# BRAIN2_Breakout_SW.net
KiCad netlist of a schematic drawn in EAGLE
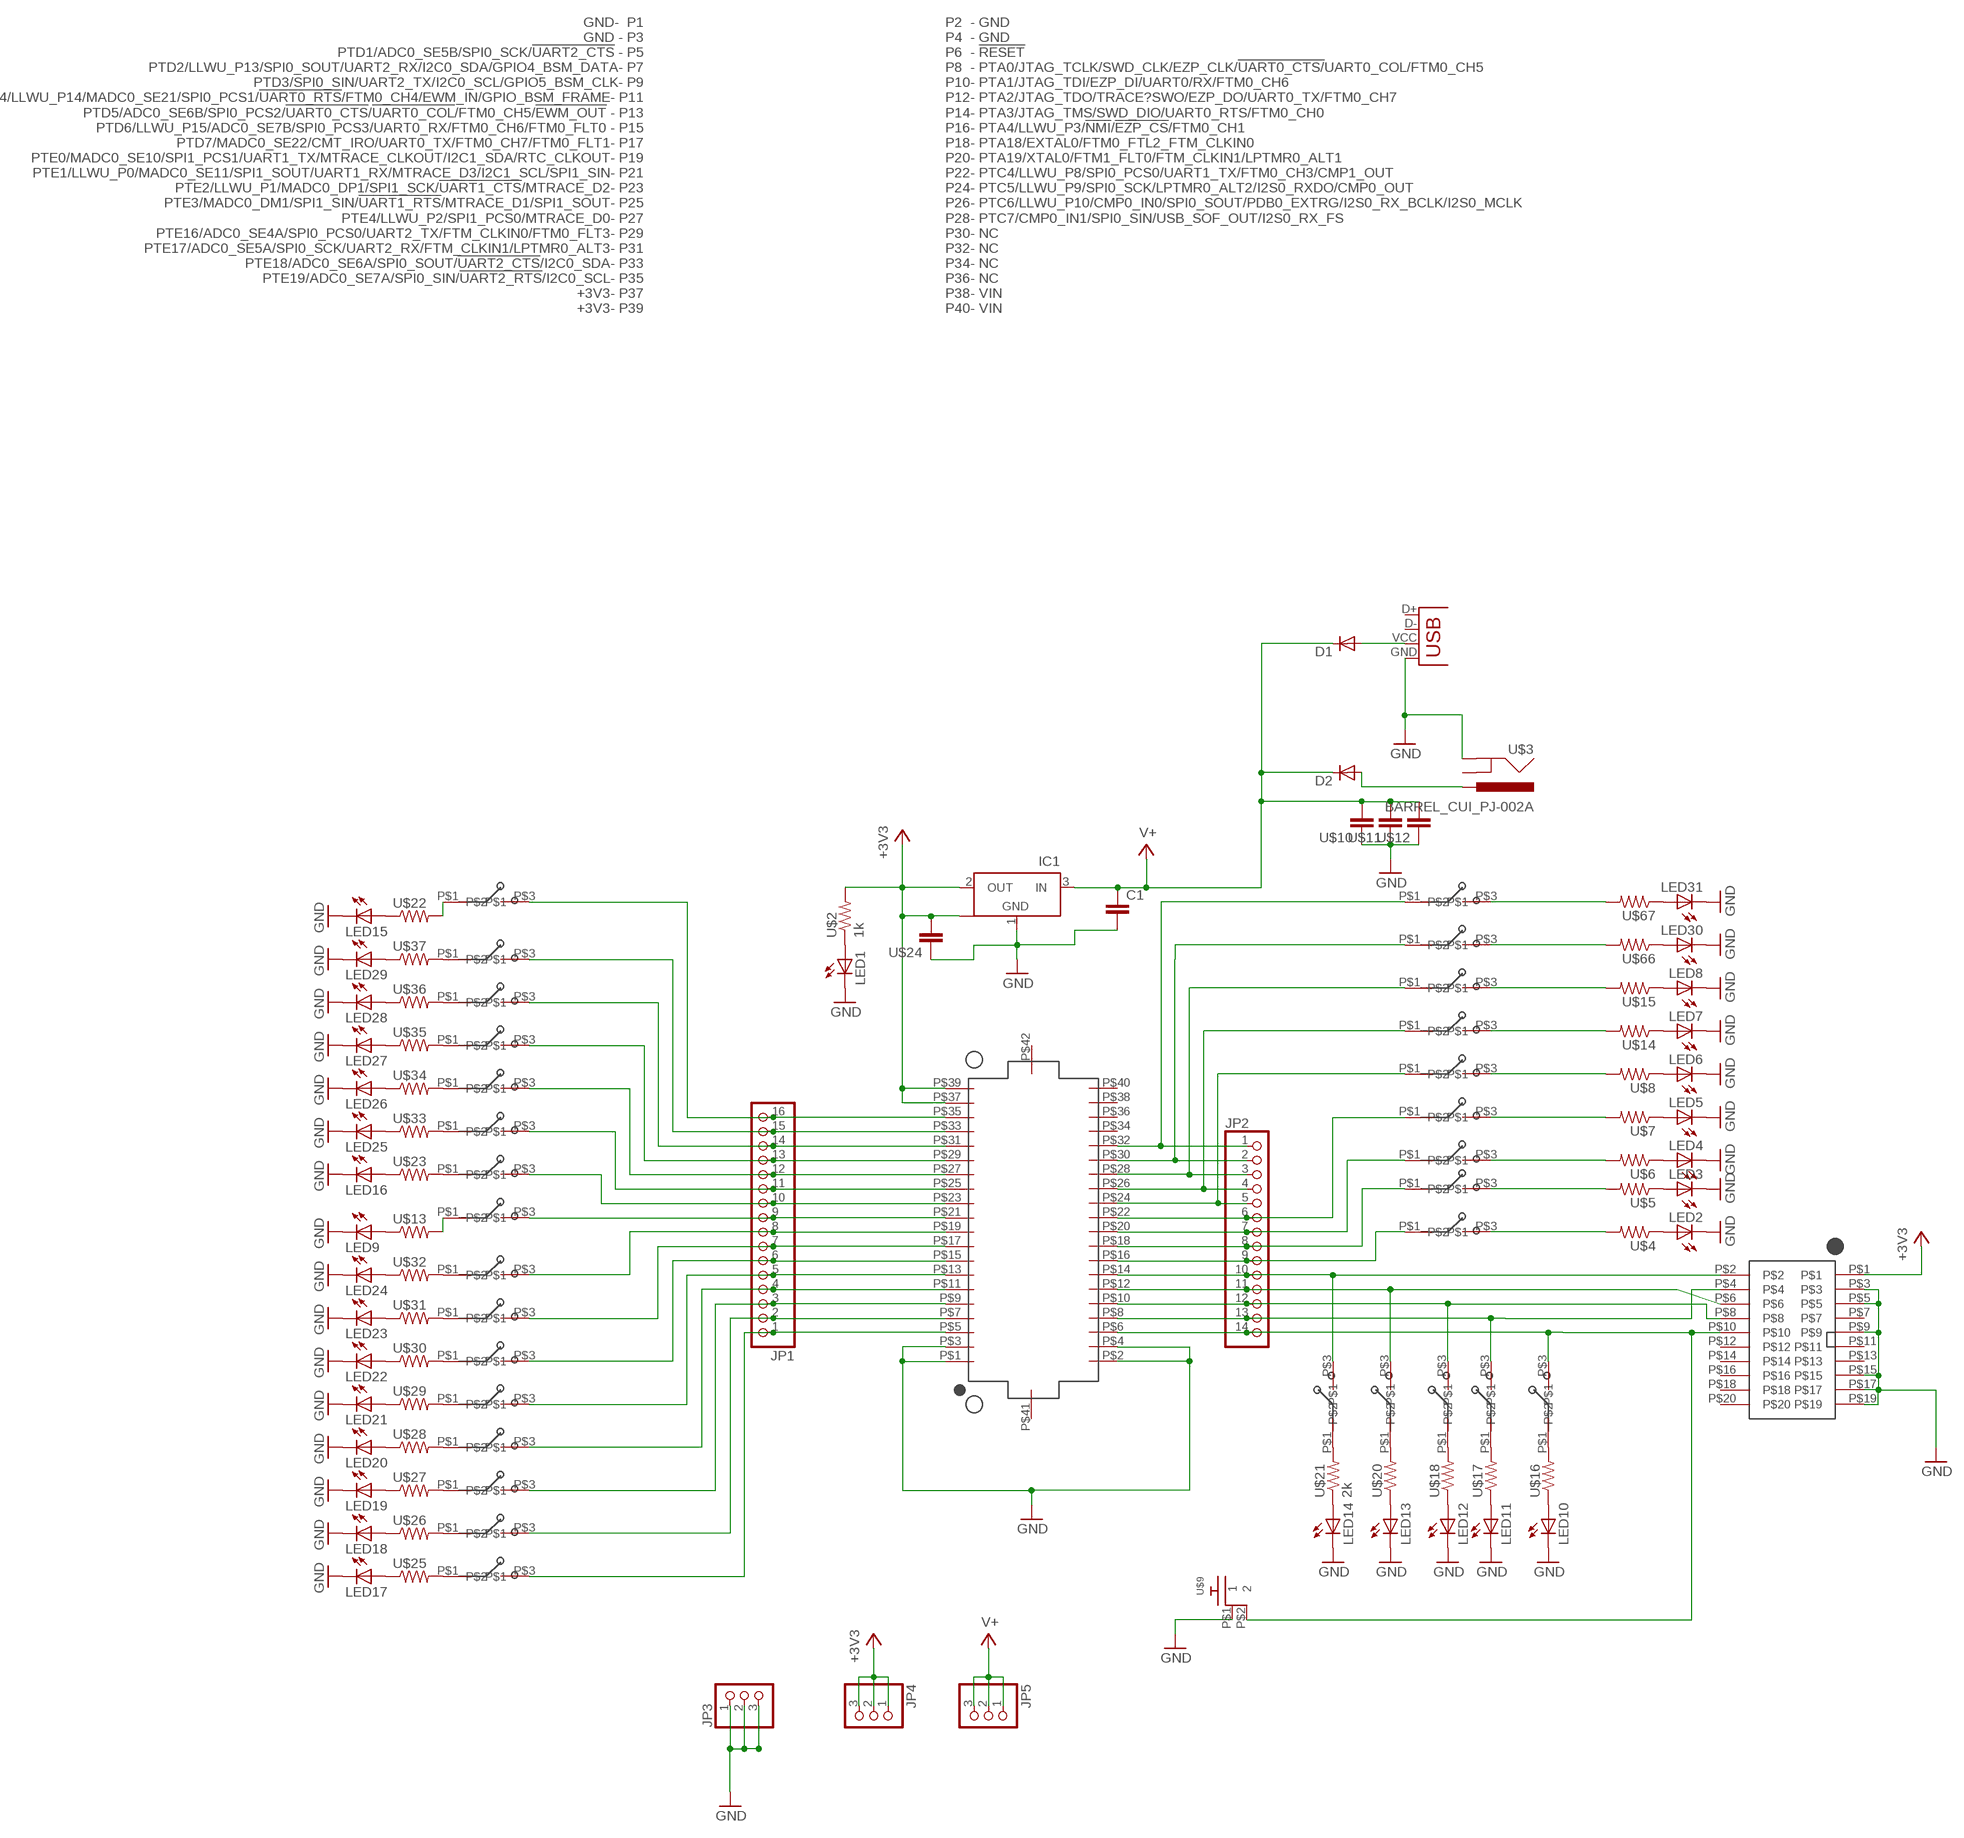
[diagram p0: schematic, sheet 1]

(export (version "E")
  (design (tool "Eeschema 10.0.6"))
  (components
    (comp (ref "C1")
      (value "RF-C0805")
      (footprint "eagle-import:C0805")
      (libsource (lib "eagle-import") (part "RF-C0805"))
    )
    (comp (ref "D1")
      (value "DIODESMA")
      (footprint "eagle-import:SMA-DIODE")
      (libsource (lib "eagle-import") (part "DIODESMA"))
    )
    (comp (ref "D2")
      (value "DIODESMA")
      (footprint "eagle-import:SMA-DIODE")
      (libsource (lib "eagle-import") (part "DIODESMA"))
    )
    (comp (ref "IC1")
      (value "NCP1117ST33T3G_1")
      (footprint "eagle-import:SOT223")
      (fields (field (name "MFGN") "OnSemi") (field (name "MFGP") "NCP1117ST33T3G"))
      (libsource (lib "eagle-import") (part "NCP1117ST33T3G_1"))
    )
    (comp (ref "JP1")
      (value "PINHD-1X16")
      (footprint "eagle-import:1X16")
      (libsource (lib "eagle-import") (part "PINHD-1X16"))
    )
    (comp (ref "JP2")
      (value "PINHD-1X14")
      (footprint "eagle-import:1X14")
      (libsource (lib "eagle-import") (part "PINHD-1X14"))
    )
    (comp (ref "JP3")
      (value "PINHD-1X3")
      (footprint "eagle-import:1X03")
      (libsource (lib "eagle-import") (part "PINHD-1X3"))
    )
    (comp (ref "JP4")
      (value "PINHD-1X3")
      (footprint "eagle-import:1X03")
      (libsource (lib "eagle-import") (part "PINHD-1X3"))
    )
    (comp (ref "JP5")
      (value "PINHD-1X3")
      (footprint "eagle-import:1X03")
      (libsource (lib "eagle-import") (part "PINHD-1X3"))
    )
    (comp (ref "LED1")
      (value "LEDCHIP-LED0805")
      (footprint "eagle-import:CHIP-LED0805")
      (fields (field (name "MFGN") "Wurth Electronics Inc") (field (name "MFGP") "150080BS75000"))
      (libsource (lib "eagle-import") (part "LEDCHIP-LED0805"))
    )
    (comp (ref "LED2")
      (value "LEDCHIP-LED0805")
      (footprint "eagle-import:CHIP-LED0805")
      (libsource (lib "eagle-import") (part "LEDCHIP-LED0805"))
    )
    (comp (ref "LED3")
      (value "LEDCHIP-LED0805")
      (footprint "eagle-import:CHIP-LED0805")
      (libsource (lib "eagle-import") (part "LEDCHIP-LED0805"))
    )
    (comp (ref "LED4")
      (value "LEDCHIP-LED0805")
      (footprint "eagle-import:CHIP-LED0805")
      (libsource (lib "eagle-import") (part "LEDCHIP-LED0805"))
    )
    (comp (ref "LED5")
      (value "LEDCHIP-LED0805")
      (footprint "eagle-import:CHIP-LED0805")
      (libsource (lib "eagle-import") (part "LEDCHIP-LED0805"))
    )
    (comp (ref "LED6")
      (value "LEDCHIP-LED0805")
      (footprint "eagle-import:CHIP-LED0805")
      (libsource (lib "eagle-import") (part "LEDCHIP-LED0805"))
    )
    (comp (ref "LED7")
      (value "LEDCHIP-LED0805")
      (footprint "eagle-import:CHIP-LED0805")
      (libsource (lib "eagle-import") (part "LEDCHIP-LED0805"))
    )
    (comp (ref "LED8")
      (value "LEDCHIP-LED0805")
      (footprint "eagle-import:CHIP-LED0805")
      (libsource (lib "eagle-import") (part "LEDCHIP-LED0805"))
    )
    (comp (ref "LED9")
      (value "LEDCHIP-LED0805")
      (footprint "eagle-import:CHIP-LED0805")
      (libsource (lib "eagle-import") (part "LEDCHIP-LED0805"))
    )
    (comp (ref "LED10")
      (value "LEDCHIP-LED0805")
      (footprint "eagle-import:CHIP-LED0805")
      (libsource (lib "eagle-import") (part "LEDCHIP-LED0805"))
    )
    (comp (ref "LED11")
      (value "LEDCHIP-LED0805")
      (footprint "eagle-import:CHIP-LED0805")
      (libsource (lib "eagle-import") (part "LEDCHIP-LED0805"))
    )
    (comp (ref "LED12")
      (value "LEDCHIP-LED0805")
      (footprint "eagle-import:CHIP-LED0805")
      (libsource (lib "eagle-import") (part "LEDCHIP-LED0805"))
    )
    (comp (ref "LED13")
      (value "LEDCHIP-LED0805")
      (footprint "eagle-import:CHIP-LED0805")
      (libsource (lib "eagle-import") (part "LEDCHIP-LED0805"))
    )
    (comp (ref "LED14")
      (value "LEDCHIP-LED0805")
      (footprint "eagle-import:CHIP-LED0805")
      (libsource (lib "eagle-import") (part "LEDCHIP-LED0805"))
    )
    (comp (ref "LED15")
      (value "LEDCHIP-LED0805")
      (footprint "eagle-import:CHIP-LED0805")
      (fields (field (name "MFGN") "Kingbright") (field (name "MFGP") "APT2012SECK"))
      (libsource (lib "eagle-import") (part "LEDCHIP-LED0805"))
    )
    (comp (ref "LED16")
      (value "LEDCHIP-LED0805")
      (footprint "eagle-import:CHIP-LED0805")
      (libsource (lib "eagle-import") (part "LEDCHIP-LED0805"))
    )
    (comp (ref "LED17")
      (value "LEDCHIP-LED0805")
      (footprint "eagle-import:CHIP-LED0805")
      (libsource (lib "eagle-import") (part "LEDCHIP-LED0805"))
    )
    (comp (ref "LED18")
      (value "LEDCHIP-LED0805")
      (footprint "eagle-import:CHIP-LED0805")
      (libsource (lib "eagle-import") (part "LEDCHIP-LED0805"))
    )
    (comp (ref "LED19")
      (value "LEDCHIP-LED0805")
      (footprint "eagle-import:CHIP-LED0805")
      (libsource (lib "eagle-import") (part "LEDCHIP-LED0805"))
    )
    (comp (ref "LED20")
      (value "LEDCHIP-LED0805")
      (footprint "eagle-import:CHIP-LED0805")
      (libsource (lib "eagle-import") (part "LEDCHIP-LED0805"))
    )
    (comp (ref "LED21")
      (value "LEDCHIP-LED0805")
      (footprint "eagle-import:CHIP-LED0805")
      (libsource (lib "eagle-import") (part "LEDCHIP-LED0805"))
    )
    (comp (ref "LED22")
      (value "LEDCHIP-LED0805")
      (footprint "eagle-import:CHIP-LED0805")
      (libsource (lib "eagle-import") (part "LEDCHIP-LED0805"))
    )
    (comp (ref "LED23")
      (value "LEDCHIP-LED0805")
      (footprint "eagle-import:CHIP-LED0805")
      (libsource (lib "eagle-import") (part "LEDCHIP-LED0805"))
    )
    (comp (ref "LED24")
      (value "LEDCHIP-LED0805")
      (footprint "eagle-import:CHIP-LED0805")
      (libsource (lib "eagle-import") (part "LEDCHIP-LED0805"))
    )
    (comp (ref "LED25")
      (value "LEDCHIP-LED0805")
      (footprint "eagle-import:CHIP-LED0805")
      (libsource (lib "eagle-import") (part "LEDCHIP-LED0805"))
    )
    (comp (ref "LED26")
      (value "LEDCHIP-LED0805")
      (footprint "eagle-import:CHIP-LED0805")
      (libsource (lib "eagle-import") (part "LEDCHIP-LED0805"))
    )
    (comp (ref "LED27")
      (value "LEDCHIP-LED0805")
      (footprint "eagle-import:CHIP-LED0805")
      (libsource (lib "eagle-import") (part "LEDCHIP-LED0805"))
    )
    (comp (ref "LED28")
      (value "LEDCHIP-LED0805")
      (footprint "eagle-import:CHIP-LED0805")
      (libsource (lib "eagle-import") (part "LEDCHIP-LED0805"))
    )
    (comp (ref "LED29")
      (value "LEDCHIP-LED0805")
      (footprint "eagle-import:CHIP-LED0805")
      (libsource (lib "eagle-import") (part "LEDCHIP-LED0805"))
    )
    (comp (ref "LED30")
      (value "LEDCHIP-LED0805")
      (footprint "eagle-import:CHIP-LED0805")
      (libsource (lib "eagle-import") (part "LEDCHIP-LED0805"))
    )
    (comp (ref "LED31")
      (value "LEDCHIP-LED0805")
      (footprint "eagle-import:CHIP-LED0805")
      (libsource (lib "eagle-import") (part "LEDCHIP-LED0805"))
    )
    (comp (ref "U$1")
      (value "KW2_CPU_NEW")
      (footprint "eagle-import:BRAIN_NEW")
      (libsource (lib "eagle-import") (part "KW2_CPU_NEW"))
    )
    (comp (ref "U$2")
      (value "1k")
      (footprint "eagle-import:RF-C0805")
      (libsource (lib "eagle-import") (part "RF-R0805"))
    )
    (comp (ref "U$3")
      (value "BARREL_CUI_PJ-002A")
      (footprint "eagle-import:BARREL_CUI_PJ-002A")
      (libsource (lib "eagle-import") (part "BARREL_CUI_PJ-002A"))
    )
    (comp (ref "U$4")
      (value "RF-R0805")
      (footprint "eagle-import:RF-C0805")
      (libsource (lib "eagle-import") (part "RF-R0805"))
    )
    (comp (ref "U$5")
      (value "RF-R0805")
      (footprint "eagle-import:RF-C0805")
      (libsource (lib "eagle-import") (part "RF-R0805"))
    )
    (comp (ref "U$6")
      (value "RF-R0805")
      (footprint "eagle-import:RF-C0805")
      (libsource (lib "eagle-import") (part "RF-R0805"))
    )
    (comp (ref "U$7")
      (value "RF-R0805")
      (footprint "eagle-import:RF-C0805")
      (libsource (lib "eagle-import") (part "RF-R0805"))
    )
    (comp (ref "U$8")
      (value "RF-R0805")
      (footprint "eagle-import:RF-C0805")
      (libsource (lib "eagle-import") (part "RF-R0805"))
    )
    (comp (ref "U$9")
      (value "RA_BUTTON")
      (footprint "eagle-import:RA_BUTTON")
      (libsource (lib "eagle-import") (part "RA_BUTTON"))
    )
    (comp (ref "U$10")
      (value "RF-C0805")
      (footprint "eagle-import:C0805")
      (libsource (lib "eagle-import") (part "RF-C0805"))
    )
    (comp (ref "U$11")
      (value "RF-C0805")
      (footprint "eagle-import:C0805")
      (libsource (lib "eagle-import") (part "RF-C0805"))
    )
    (comp (ref "U$12")
      (value "RF-C0805")
      (footprint "eagle-import:C0805")
      (libsource (lib "eagle-import") (part "RF-C0805"))
    )
    (comp (ref "U$13")
      (value "RF-R0805")
      (footprint "eagle-import:RF-C0805")
      (libsource (lib "eagle-import") (part "RF-R0805"))
    )
    (comp (ref "U$14")
      (value "RF-R0805")
      (footprint "eagle-import:RF-C0805")
      (libsource (lib "eagle-import") (part "RF-R0805"))
    )
    (comp (ref "U$15")
      (value "RF-R0805")
      (footprint "eagle-import:RF-C0805")
      (libsource (lib "eagle-import") (part "RF-R0805"))
    )
    (comp (ref "U$16")
      (value "RF-R0805")
      (footprint "eagle-import:RF-C0805")
      (libsource (lib "eagle-import") (part "RF-R0805"))
    )
    (comp (ref "U$17")
      (value "RF-R0805")
      (footprint "eagle-import:RF-C0805")
      (libsource (lib "eagle-import") (part "RF-R0805"))
    )
    (comp (ref "U$18")
      (value "RF-R0805")
      (footprint "eagle-import:RF-C0805")
      (libsource (lib "eagle-import") (part "RF-R0805"))
    )
    (comp (ref "U$19")
      (value "2X10JTAG")
      (footprint "eagle-import:2X10JTAG")
      (libsource (lib "eagle-import") (part "2X10JTAG"))
    )
    (comp (ref "U$20")
      (value "RF-R0805")
      (footprint "eagle-import:RF-C0805")
      (libsource (lib "eagle-import") (part "RF-R0805"))
    )
    (comp (ref "U$21")
      (value "2k")
      (footprint "eagle-import:RF-C0805")
      (libsource (lib "eagle-import") (part "RF-R0805"))
    )
    (comp (ref "U$22")
      (value "RF-R0805")
      (footprint "eagle-import:RF-C0805")
      (libsource (lib "eagle-import") (part "RF-R0805"))
    )
    (comp (ref "U$23")
      (value "RF-R0805")
      (footprint "eagle-import:RF-C0805")
      (libsource (lib "eagle-import") (part "RF-R0805"))
    )
    (comp (ref "U$24")
      (value "RF-C0805")
      (footprint "eagle-import:C0805")
      (libsource (lib "eagle-import") (part "RF-C0805"))
    )
    (comp (ref "U$25")
      (value "RF-R0805")
      (footprint "eagle-import:RF-C0805")
      (libsource (lib "eagle-import") (part "RF-R0805"))
    )
    (comp (ref "U$26")
      (value "RF-R0805")
      (footprint "eagle-import:RF-C0805")
      (libsource (lib "eagle-import") (part "RF-R0805"))
    )
    (comp (ref "U$27")
      (value "RF-R0805")
      (footprint "eagle-import:RF-C0805")
      (libsource (lib "eagle-import") (part "RF-R0805"))
    )
    (comp (ref "U$28")
      (value "RF-R0805")
      (footprint "eagle-import:RF-C0805")
      (libsource (lib "eagle-import") (part "RF-R0805"))
    )
    (comp (ref "U$29")
      (value "RF-R0805")
      (footprint "eagle-import:RF-C0805")
      (libsource (lib "eagle-import") (part "RF-R0805"))
    )
    (comp (ref "U$30")
      (value "RF-R0805")
      (footprint "eagle-import:RF-C0805")
      (libsource (lib "eagle-import") (part "RF-R0805"))
    )
    (comp (ref "U$31")
      (value "RF-R0805")
      (footprint "eagle-import:RF-C0805")
      (libsource (lib "eagle-import") (part "RF-R0805"))
    )
    (comp (ref "U$32")
      (value "RF-R0805")
      (footprint "eagle-import:RF-C0805")
      (libsource (lib "eagle-import") (part "RF-R0805"))
    )
    (comp (ref "U$33")
      (value "RF-R0805")
      (footprint "eagle-import:RF-C0805")
      (libsource (lib "eagle-import") (part "RF-R0805"))
    )
    (comp (ref "U$34")
      (value "RF-R0805")
      (footprint "eagle-import:RF-C0805")
      (libsource (lib "eagle-import") (part "RF-R0805"))
    )
    (comp (ref "U$35")
      (value "RF-R0805")
      (footprint "eagle-import:RF-C0805")
      (libsource (lib "eagle-import") (part "RF-R0805"))
    )
    (comp (ref "U$36")
      (value "RF-R0805")
      (footprint "eagle-import:RF-C0805")
      (libsource (lib "eagle-import") (part "RF-R0805"))
    )
    (comp (ref "U$37")
      (value "RF-R0805")
      (footprint "eagle-import:RF-C0805")
      (libsource (lib "eagle-import") (part "RF-R0805"))
    )
    (comp (ref "U$38")
      (value "CJS")
      (footprint "eagle-import:CJS")
      (libsource (lib "eagle-import") (part "CJS"))
    )
    (comp (ref "U$39")
      (value "CJS")
      (footprint "eagle-import:CJS")
      (libsource (lib "eagle-import") (part "CJS"))
    )
    (comp (ref "U$40")
      (value "CJS")
      (footprint "eagle-import:CJS")
      (libsource (lib "eagle-import") (part "CJS"))
    )
    (comp (ref "U$41")
      (value "CJS")
      (footprint "eagle-import:CJS")
      (libsource (lib "eagle-import") (part "CJS"))
    )
    (comp (ref "U$42")
      (value "CJS")
      (footprint "eagle-import:CJS")
      (libsource (lib "eagle-import") (part "CJS"))
    )
    (comp (ref "U$43")
      (value "CJS")
      (footprint "eagle-import:CJS")
      (libsource (lib "eagle-import") (part "CJS"))
    )
    (comp (ref "U$44")
      (value "CJS")
      (footprint "eagle-import:CJS")
      (libsource (lib "eagle-import") (part "CJS"))
    )
    (comp (ref "U$45")
      (value "CJS")
      (footprint "eagle-import:CJS")
      (libsource (lib "eagle-import") (part "CJS"))
    )
    (comp (ref "U$46")
      (value "CJS")
      (footprint "eagle-import:CJS")
      (libsource (lib "eagle-import") (part "CJS"))
    )
    (comp (ref "U$47")
      (value "CJS")
      (footprint "eagle-import:CJS")
      (libsource (lib "eagle-import") (part "CJS"))
    )
    (comp (ref "U$48")
      (value "CJS")
      (footprint "eagle-import:CJS")
      (libsource (lib "eagle-import") (part "CJS"))
    )
    (comp (ref "U$49")
      (value "CJS")
      (footprint "eagle-import:CJS")
      (libsource (lib "eagle-import") (part "CJS"))
    )
    (comp (ref "U$50")
      (value "CJS")
      (footprint "eagle-import:CJS")
      (libsource (lib "eagle-import") (part "CJS"))
    )
    (comp (ref "U$51")
      (value "CJS")
      (footprint "eagle-import:CJS")
      (libsource (lib "eagle-import") (part "CJS"))
    )
    (comp (ref "U$52")
      (value "CJS")
      (footprint "eagle-import:CJS")
      (libsource (lib "eagle-import") (part "CJS"))
    )
    (comp (ref "U$53")
      (value "CJS")
      (footprint "eagle-import:CJS")
      (libsource (lib "eagle-import") (part "CJS"))
    )
    (comp (ref "U$54")
      (value "CJS")
      (footprint "eagle-import:CJS")
      (libsource (lib "eagle-import") (part "CJS"))
    )
    (comp (ref "U$55")
      (value "CJS")
      (footprint "eagle-import:CJS")
      (libsource (lib "eagle-import") (part "CJS"))
    )
    (comp (ref "U$56")
      (value "CJS")
      (footprint "eagle-import:CJS")
      (libsource (lib "eagle-import") (part "CJS"))
    )
    (comp (ref "U$57")
      (value "CJS")
      (footprint "eagle-import:CJS")
      (libsource (lib "eagle-import") (part "CJS"))
    )
    (comp (ref "U$58")
      (value "CJS")
      (footprint "eagle-import:CJS")
      (libsource (lib "eagle-import") (part "CJS"))
    )
    (comp (ref "U$59")
      (value "CJS")
      (footprint "eagle-import:CJS")
      (libsource (lib "eagle-import") (part "CJS"))
    )
    (comp (ref "U$60")
      (value "CJS")
      (footprint "eagle-import:CJS")
      (libsource (lib "eagle-import") (part "CJS"))
    )
    (comp (ref "U$61")
      (value "CJS")
      (footprint "eagle-import:CJS")
      (libsource (lib "eagle-import") (part "CJS"))
    )
    (comp (ref "U$62")
      (value "CJS")
      (footprint "eagle-import:CJS")
      (libsource (lib "eagle-import") (part "CJS"))
    )
    (comp (ref "U$63")
      (value "CJS")
      (footprint "eagle-import:CJS")
      (libsource (lib "eagle-import") (part "CJS"))
    )
    (comp (ref "U$64")
      (value "CJS")
      (footprint "eagle-import:CJS")
      (libsource (lib "eagle-import") (part "CJS"))
    )
    (comp (ref "U$65")
      (value "CJS")
      (footprint "eagle-import:CJS")
      (libsource (lib "eagle-import") (part "CJS"))
    )
    (comp (ref "U$66")
      (value "RF-R0805")
      (footprint "eagle-import:RF-C0805")
      (libsource (lib "eagle-import") (part "RF-R0805"))
    )
    (comp (ref "U$67")
      (value "RF-R0805")
      (footprint "eagle-import:RF-C0805")
      (libsource (lib "eagle-import") (part "RF-R0805"))
    )
    (comp (ref "U$68")
      (value "CJS")
      (footprint "eagle-import:CJS")
      (libsource (lib "eagle-import") (part "CJS"))
    )
    (comp (ref "U$69")
      (value "CJS")
      (footprint "eagle-import:CJS")
      (libsource (lib "eagle-import") (part "CJS"))
    )
    (comp (ref "X1")
      (value "USB")
      (footprint "eagle-import:USB3076-30-A")
      (libsource (lib "eagle-import") (part "USB"))
    )
  )
  (nets
    (net (code "1") (name "+3V3") (class "Default")
      (node (ref "IC1") (pin "2") (pinfunction "OUT_2") (pintype "power_in"))
      (node (ref "IC1") (pin "4") (pinfunction "OUT1_4") (pintype "power_in"))
      (node (ref "JP4") (pin "1") (pinfunction "1_1") (pintype "passive"))
      (node (ref "JP4") (pin "2") (pinfunction "2_2") (pintype "passive"))
      (node (ref "JP4") (pin "3") (pinfunction "3_3") (pintype "passive"))
      (node (ref "U$1") (pin "P$37") (pinfunction "+3V3_P$37") (pintype "bidirectional"))
      (node (ref "U$1") (pin "P$39") (pinfunction "+3V3_P$39") (pintype "bidirectional"))
      (node (ref "U$19") (pin "P$1") (pinfunction "P$1_P$1") (pintype "bidirectional"))
      (node (ref "U$2") (pin "2") (pinfunction "2_2") (pintype "passive"))
      (node (ref "U$24") (pin "2") (pinfunction "2_2") (pintype "passive"))
    )
    (net (code "2") (name "GND") (class "Default")
      (node (ref "C1") (pin "2") (pinfunction "2_2") (pintype "passive"))
      (node (ref "IC1") (pin "1") (pinfunction "GND_1") (pintype "power_in"))
      (node (ref "JP3") (pin "1") (pinfunction "1_1") (pintype "passive"))
      (node (ref "JP3") (pin "2") (pinfunction "2_2") (pintype "passive"))
      (node (ref "JP3") (pin "3") (pinfunction "3_3") (pintype "passive"))
      (node (ref "LED1") (pin "C") (pinfunction "C_C") (pintype "passive"))
      (node (ref "LED10") (pin "C") (pinfunction "C_C") (pintype "passive"))
      (node (ref "LED11") (pin "C") (pinfunction "C_C") (pintype "passive"))
      (node (ref "LED12") (pin "C") (pinfunction "C_C") (pintype "passive"))
      (node (ref "LED13") (pin "C") (pinfunction "C_C") (pintype "passive"))
      (node (ref "LED14") (pin "C") (pinfunction "C_C") (pintype "passive"))
      (node (ref "LED15") (pin "C") (pinfunction "C_C") (pintype "passive"))
      (node (ref "LED16") (pin "C") (pinfunction "C_C") (pintype "passive"))
      (node (ref "LED17") (pin "C") (pinfunction "C_C") (pintype "passive"))
      (node (ref "LED18") (pin "C") (pinfunction "C_C") (pintype "passive"))
      (node (ref "LED19") (pin "C") (pinfunction "C_C") (pintype "passive"))
      (node (ref "LED2") (pin "C") (pinfunction "C_C") (pintype "passive"))
      (node (ref "LED20") (pin "C") (pinfunction "C_C") (pintype "passive"))
      (node (ref "LED21") (pin "C") (pinfunction "C_C") (pintype "passive"))
      (node (ref "LED22") (pin "C") (pinfunction "C_C") (pintype "passive"))
      (node (ref "LED23") (pin "C") (pinfunction "C_C") (pintype "passive"))
      (node (ref "LED24") (pin "C") (pinfunction "C_C") (pintype "passive"))
      (node (ref "LED25") (pin "C") (pinfunction "C_C") (pintype "passive"))
      (node (ref "LED26") (pin "C") (pinfunction "C_C") (pintype "passive"))
      (node (ref "LED27") (pin "C") (pinfunction "C_C") (pintype "passive"))
      (node (ref "LED28") (pin "C") (pinfunction "C_C") (pintype "passive"))
      (node (ref "LED29") (pin "C") (pinfunction "C_C") (pintype "passive"))
      (node (ref "LED3") (pin "C") (pinfunction "C_C") (pintype "passive"))
      (node (ref "LED30") (pin "C") (pinfunction "C_C") (pintype "passive"))
      (node (ref "LED31") (pin "C") (pinfunction "C_C") (pintype "passive"))
      (node (ref "LED4") (pin "C") (pinfunction "C_C") (pintype "passive"))
      (node (ref "LED5") (pin "C") (pinfunction "C_C") (pintype "passive"))
      (node (ref "LED6") (pin "C") (pinfunction "C_C") (pintype "passive"))
      (node (ref "LED7") (pin "C") (pinfunction "C_C") (pintype "passive"))
      (node (ref "LED8") (pin "C") (pinfunction "C_C") (pintype "passive"))
      (node (ref "LED9") (pin "C") (pinfunction "C_C") (pintype "passive"))
      (node (ref "U$1") (pin "P$1") (pinfunction "GND_P$1") (pintype "bidirectional"))
      (node (ref "U$1") (pin "P$2") (pinfunction "GND_P$2") (pintype "bidirectional"))
      (node (ref "U$1") (pin "P$3") (pinfunction "GND_P$3") (pintype "bidirectional"))
      (node (ref "U$1") (pin "P$4") (pinfunction "GND_P$4") (pintype "bidirectional"))
      (node (ref "U$10") (pin "1") (pinfunction "1_1") (pintype "passive"))
      (node (ref "U$11") (pin "1") (pinfunction "1_1") (pintype "passive"))
      (node (ref "U$12") (pin "1") (pinfunction "1_1") (pintype "passive"))
      (node (ref "U$19") (pin "P$15") (pinfunction "P$15_P$15") (pintype "bidirectional"))
      (node (ref "U$19") (pin "P$17") (pinfunction "P$17_P$17") (pintype "bidirectional"))
      (node (ref "U$19") (pin "P$19") (pinfunction "P$19_P$19") (pintype "bidirectional"))
      (node (ref "U$19") (pin "P$3") (pinfunction "P$3_P$3") (pintype "bidirectional"))
      (node (ref "U$19") (pin "P$5") (pinfunction "P$5_P$5") (pintype "bidirectional"))
      (node (ref "U$19") (pin "P$9") (pinfunction "P$9_P$9") (pintype "bidirectional"))
      (node (ref "U$24") (pin "1") (pinfunction "1_1") (pintype "passive"))
      (node (ref "U$3") (pin "P$2") (pinfunction "GND_P$2") (pintype "bidirectional"))
      (node (ref "U$9") (pin "P$1") (pinfunction "1_P$1") (pintype "input"))
      (node (ref "X1") (pin "GND") (pinfunction "GND_GND") (pintype "bidirectional"))
    )
    (net (code "3") (name "Net-(JP2-Pad1)") (class "Default")
      (node (ref "JP2") (pin "1") (pinfunction "1_1") (pintype "passive"))
      (node (ref "U$1") (pin "P$32") (pinfunction "NC_P$32") (pintype "bidirectional"))
      (node (ref "U$69") (pin "P$1") (pinfunction "P$1_P$1") (pintype "bidirectional"))
    )
    (net (code "4") (name "Net-(JP2-Pad2)") (class "Default")
      (node (ref "JP2") (pin "2") (pinfunction "2_2") (pintype "passive"))
      (node (ref "U$1") (pin "P$30") (pinfunction "NC_P$30") (pintype "bidirectional"))
      (node (ref "U$68") (pin "P$1") (pinfunction "P$1_P$1") (pintype "bidirectional"))
    )
    (net (code "5") (name "Net-(LED1-PadA)") (class "Default")
      (node (ref "LED1") (pin "A") (pinfunction "A_A") (pintype "passive"))
      (node (ref "U$2") (pin "1") (pinfunction "1_1") (pintype "passive"))
    )
    (net (code "6") (name "Net-(LED2-PadA)") (class "Default")
      (node (ref "LED2") (pin "A") (pinfunction "A_A") (pintype "passive"))
      (node (ref "U$4") (pin "1") (pinfunction "1_1") (pintype "passive"))
    )
    (net (code "7") (name "Net-(LED3-PadA)") (class "Default")
      (node (ref "LED3") (pin "A") (pinfunction "A_A") (pintype "passive"))
      (node (ref "U$5") (pin "1") (pinfunction "1_1") (pintype "passive"))
    )
    (net (code "8") (name "Net-(LED4-PadA)") (class "Default")
      (node (ref "LED4") (pin "A") (pinfunction "A_A") (pintype "passive"))
      (node (ref "U$6") (pin "1") (pinfunction "1_1") (pintype "passive"))
    )
    (net (code "9") (name "Net-(LED5-PadA)") (class "Default")
      (node (ref "LED5") (pin "A") (pinfunction "A_A") (pintype "passive"))
      (node (ref "U$7") (pin "1") (pinfunction "1_1") (pintype "passive"))
    )
    (net (code "10") (name "Net-(LED6-PadA)") (class "Default")
      (node (ref "LED6") (pin "A") (pinfunction "A_A") (pintype "passive"))
      (node (ref "U$8") (pin "1") (pinfunction "1_1") (pintype "passive"))
    )
    (net (code "11") (name "Net-(LED7-PadA)") (class "Default")
      (node (ref "LED7") (pin "A") (pinfunction "A_A") (pintype "passive"))
      (node (ref "U$14") (pin "1") (pinfunction "1_1") (pintype "passive"))
    )
    (net (code "12") (name "Net-(LED8-PadA)") (class "Default")
      (node (ref "LED8") (pin "A") (pinfunction "A_A") (pintype "passive"))
      (node (ref "U$15") (pin "1") (pinfunction "1_1") (pintype "passive"))
    )
    (net (code "13") (name "Net-(LED9-PadA)") (class "Default")
      (node (ref "LED9") (pin "A") (pinfunction "A_A") (pintype "passive"))
      (node (ref "U$13") (pin "1") (pinfunction "1_1") (pintype "passive"))
    )
    (net (code "14") (name "Net-(LED10-PadA)") (class "Default")
      (node (ref "LED10") (pin "A") (pinfunction "A_A") (pintype "passive"))
      (node (ref "U$16") (pin "1") (pinfunction "1_1") (pintype "passive"))
    )
    (net (code "15") (name "Net-(LED11-PadA)") (class "Default")
      (node (ref "LED11") (pin "A") (pinfunction "A_A") (pintype "passive"))
      (node (ref "U$17") (pin "1") (pinfunction "1_1") (pintype "passive"))
    )
    (net (code "16") (name "Net-(LED12-PadA)") (class "Default")
      (node (ref "LED12") (pin "A") (pinfunction "A_A") (pintype "passive"))
      (node (ref "U$18") (pin "1") (pinfunction "1_1") (pintype "passive"))
    )
    (net (code "17") (name "Net-(LED13-PadA)") (class "Default")
      (node (ref "LED13") (pin "A") (pinfunction "A_A") (pintype "passive"))
      (node (ref "U$20") (pin "1") (pinfunction "1_1") (pintype "passive"))
    )
    (net (code "18") (name "Net-(LED14-PadA)") (class "Default")
      (node (ref "LED14") (pin "A") (pinfunction "A_A") (pintype "passive"))
      (node (ref "U$21") (pin "1") (pinfunction "1_1") (pintype "passive"))
    )
    (net (code "19") (name "Net-(LED15-PadA)") (class "Default")
      (node (ref "LED15") (pin "A") (pinfunction "A_A") (pintype "passive"))
      (node (ref "U$22") (pin "1") (pinfunction "1_1") (pintype "passive"))
    )
    (net (code "20") (name "Net-(LED16-PadA)") (class "Default")
      (node (ref "LED16") (pin "A") (pinfunction "A_A") (pintype "passive"))
      (node (ref "U$23") (pin "1") (pinfunction "1_1") (pintype "passive"))
    )
    (net (code "21") (name "Net-(LED17-PadA)") (class "Default")
      (node (ref "LED17") (pin "A") (pinfunction "A_A") (pintype "passive"))
      (node (ref "U$25") (pin "1") (pinfunction "1_1") (pintype "passive"))
    )
    (net (code "22") (name "Net-(LED18-PadA)") (class "Default")
      (node (ref "LED18") (pin "A") (pinfunction "A_A") (pintype "passive"))
      (node (ref "U$26") (pin "1") (pinfunction "1_1") (pintype "passive"))
    )
    (net (code "23") (name "Net-(LED19-PadA)") (class "Default")
      (node (ref "LED19") (pin "A") (pinfunction "A_A") (pintype "passive"))
      (node (ref "U$27") (pin "1") (pinfunction "1_1") (pintype "passive"))
    )
    (net (code "24") (name "Net-(LED20-PadA)") (class "Default")
      (node (ref "LED20") (pin "A") (pinfunction "A_A") (pintype "passive"))
      (node (ref "U$28") (pin "1") (pinfunction "1_1") (pintype "passive"))
    )
    (net (code "25") (name "Net-(LED21-PadA)") (class "Default")
      (node (ref "LED21") (pin "A") (pinfunction "A_A") (pintype "passive"))
      (node (ref "U$29") (pin "1") (pinfunction "1_1") (pintype "passive"))
    )
    (net (code "26") (name "Net-(LED22-PadA)") (class "Default")
      (node (ref "LED22") (pin "A") (pinfunction "A_A") (pintype "passive"))
      (node (ref "U$30") (pin "1") (pinfunction "1_1") (pintype "passive"))
    )
    (net (code "27") (name "Net-(LED23-PadA)") (class "Default")
      (node (ref "LED23") (pin "A") (pinfunction "A_A") (pintype "passive"))
      (node (ref "U$31") (pin "1") (pinfunction "1_1") (pintype "passive"))
    )
    (net (code "28") (name "Net-(LED24-PadA)") (class "Default")
      (node (ref "LED24") (pin "A") (pinfunction "A_A") (pintype "passive"))
      (node (ref "U$32") (pin "1") (pinfunction "1_1") (pintype "passive"))
    )
    (net (code "29") (name "Net-(LED25-PadA)") (class "Default")
      (node (ref "LED25") (pin "A") (pinfunction "A_A") (pintype "passive"))
      (node (ref "U$33") (pin "1") (pinfunction "1_1") (pintype "passive"))
    )
    (net (code "30") (name "Net-(LED26-PadA)") (class "Default")
      (node (ref "LED26") (pin "A") (pinfunction "A_A") (pintype "passive"))
      (node (ref "U$34") (pin "1") (pinfunction "1_1") (pintype "passive"))
    )
    (net (code "31") (name "Net-(LED27-PadA)") (class "Default")
      (node (ref "LED27") (pin "A") (pinfunction "A_A") (pintype "passive"))
      (node (ref "U$35") (pin "1") (pinfunction "1_1") (pintype "passive"))
    )
    (net (code "32") (name "Net-(LED28-PadA)") (class "Default")
      (node (ref "LED28") (pin "A") (pinfunction "A_A") (pintype "passive"))
      (node (ref "U$36") (pin "1") (pinfunction "1_1") (pintype "passive"))
    )
    (net (code "33") (name "Net-(LED29-PadA)") (class "Default")
      (node (ref "LED29") (pin "A") (pinfunction "A_A") (pintype "passive"))
      (node (ref "U$37") (pin "1") (pinfunction "1_1") (pintype "passive"))
    )
    (net (code "34") (name "Net-(LED30-PadA)") (class "Default")
      (node (ref "LED30") (pin "A") (pinfunction "A_A") (pintype "passive"))
      (node (ref "U$66") (pin "1") (pinfunction "1_1") (pintype "passive"))
    )
    (net (code "35") (name "Net-(LED31-PadA)") (class "Default")
      (node (ref "LED31") (pin "A") (pinfunction "A_A") (pintype "passive"))
      (node (ref "U$67") (pin "1") (pinfunction "1_1") (pintype "passive"))
    )
    (net (code "36") (name "Net-(U$1-PTA0{slash}JTAG_TCLK{slash}SWD_CLK{slash}EZP_CLK{slash}~{UART0_CTS{slash}}UART0_COL{slash}FTM0_CH5)") (class "Default")
      (node (ref "JP2") (pin "13") (pinfunction "13_13") (pintype "passive"))
      (node (ref "U$1") (pin "P$8") (pinfunction "PTA0/JTAG_TCLK/SWD_CLK/EZP_CLK/~{UART0_CTS/}UART0_COL/FTM0_CH5_P$8") (pintype "bidirectional"))
      (node (ref "U$19") (pin "P$4") (pinfunction "P$4_P$4") (pintype "bidirectional"))
      (node (ref "U$55") (pin "P$3") (pinfunction "P$2_P$3") (pintype "bidirectional"))
    )
    (net (code "37") (name "Net-(U$1-PTA1{slash}JTAG_TDI{slash}EZP_DI{slash}UART0{slash}RX{slash}FTM0_CH6)") (class "Default")
      (node (ref "JP2") (pin "12") (pinfunction "12_12") (pintype "passive"))
      (node (ref "U$1") (pin "P$10") (pinfunction "PTA1/JTAG_TDI/EZP_DI/UART0/RX/FTM0_CH6_P$10") (pintype "bidirectional"))
      (node (ref "U$19") (pin "P$8") (pinfunction "P$8_P$8") (pintype "bidirectional"))
      (node (ref "U$56") (pin "P$3") (pinfunction "P$2_P$3") (pintype "bidirectional"))
    )
    (net (code "38") (name "Net-(U$1-PTA2{slash}JTAG_TDO{slash}TRACE?SWO{slash}EZP_DO{slash}UART0_TX{slash}FTM0_CH7)") (class "Default")
      (node (ref "JP2") (pin "11") (pinfunction "11_11") (pintype "passive"))
      (node (ref "U$1") (pin "P$12") (pinfunction "PTA2/JTAG_TDO/TRACE?SWO/EZP_DO/UART0_TX/FTM0_CH7_P$12") (pintype "bidirectional"))
      (node (ref "U$19") (pin "P$6") (pinfunction "P$6_P$6") (pintype "bidirectional"))
      (node (ref "U$57") (pin "P$3") (pinfunction "P$2_P$3") (pintype "bidirectional"))
    )
    (net (code "39") (name "Net-(U$1-PTA3{slash}JTAG_TMS{slash}SWD_DIO{slash}UART0_RTS{slash}FTM0_CH0)") (class "Default")
      (node (ref "JP2") (pin "10") (pinfunction "10_10") (pintype "passive"))
      (node (ref "U$1") (pin "P$14") (pinfunction "PTA3/JTAG_TMS/SWD_DIO/UART0_RTS/FTM0_CH0_P$14") (pintype "bidirectional"))
      (node (ref "U$19") (pin "P$2") (pinfunction "P$2_P$2") (pintype "bidirectional"))
      (node (ref "U$58") (pin "P$3") (pinfunction "P$2_P$3") (pintype "bidirectional"))
    )
    (net (code "40") (name "Net-(U$1-PTA4{slash}LLWU_P3{slash}~{NMI}{slash}~{EZP_CS}{slash}FTM0_CH1)") (class "Default")
      (node (ref "JP2") (pin "9") (pinfunction "9_9") (pintype "passive"))
      (node (ref "U$1") (pin "P$16") (pinfunction "PTA4/LLWU_P3/~{NMI}/~{EZP_CS}/FTM0_CH1_P$16") (pintype "bidirectional"))
      (node (ref "U$59") (pin "P$1") (pinfunction "P$1_P$1") (pintype "bidirectional"))
    )
    (net (code "41") (name "Net-(U$1-PTA18{slash}EXTAL0{slash}FTM0_FTL2_FTM_CLKIN0)") (class "Default")
      (node (ref "JP2") (pin "8") (pinfunction "8_8") (pintype "passive"))
      (node (ref "U$1") (pin "P$18") (pinfunction "PTA18/EXTAL0/FTM0_FTL2_FTM_CLKIN0_P$18") (pintype "bidirectional"))
      (node (ref "U$60") (pin "P$1") (pinfunction "P$1_P$1") (pintype "bidirectional"))
    )
    (net (code "42") (name "Net-(U$1-PTA19{slash}XTAL0{slash}FTM1_FLT0{slash}FTM_CLKIN1{slash}LPTMR0_ALT1)") (class "Default")
      (node (ref "JP2") (pin "7") (pinfunction "7_7") (pintype "passive"))
      (node (ref "U$1") (pin "P$20") (pinfunction "PTA19/XTAL0/FTM1_FLT0/FTM_CLKIN1/LPTMR0_ALT1_P$20") (pintype "bidirectional"))
      (node (ref "U$61") (pin "P$1") (pinfunction "P$1_P$1") (pintype "bidirectional"))
    )
    (net (code "43") (name "Net-(U$1-PTC4{slash}LLWU_P8{slash}SPI0_PCS0{slash}UART1_TX{slash}FTM0_CH3{slash}CMP1_OUT)") (class "Default")
      (node (ref "JP2") (pin "6") (pinfunction "6_6") (pintype "passive"))
      (node (ref "U$1") (pin "P$22") (pinfunction "PTC4/LLWU_P8/SPI0_PCS0/UART1_TX/FTM0_CH3/CMP1_OUT_P$22") (pintype "bidirectional"))
      (node (ref "U$62") (pin "P$1") (pinfunction "P$1_P$1") (pintype "bidirectional"))
    )
    (net (code "44") (name "Net-(U$1-PTC5{slash}LLWU_P8{slash}SPI0_PCS0{slash}UART1_TX{slash}FTM0_CH3{slash}CMP1_OUT)") (class "Default")
      (node (ref "JP2") (pin "5") (pinfunction "5_5") (pintype "passive"))
      (node (ref "U$1") (pin "P$24") (pinfunction "PTC5/LLWU_P8/SPI0_PCS0/UART1_TX/FTM0_CH3/CMP1_OUT_P$24") (pintype "bidirectional"))
      (node (ref "U$63") (pin "P$1") (pinfunction "P$1_P$1") (pintype "bidirectional"))
    )
    (net (code "45") (name "Net-(U$1-PTC6{slash}LLWU_P10{slash}CMP0_IN0{slash}SPI0_SOUT{slash}PDB0_EXTRG{slash}I2S0_RX_BCLK{slash}I2S0_MCLK)") (class "Default")
      (node (ref "JP2") (pin "4") (pinfunction "4_4") (pintype "passive"))
      (node (ref "U$1") (pin "P$26") (pinfunction "PTC6/LLWU_P10/CMP0_IN0/SPI0_SOUT/PDB0_EXTRG/I2S0_RX_BCLK/I2S0_MCLK_P$26") (pintype "bidirectional"))
      (node (ref "U$64") (pin "P$1") (pinfunction "P$1_P$1") (pintype "bidirectional"))
    )
    (net (code "46") (name "Net-(U$1-PTC7{slash}CMP0_IN1{slash}SPI0_SIN{slash}USB_SOF_OUT{slash}I2S0_RX_FS)") (class "Default")
      (node (ref "JP2") (pin "3") (pinfunction "3_3") (pintype "passive"))
      (node (ref "U$1") (pin "P$28") (pinfunction "PTC7/CMP0_IN1/SPI0_SIN/USB_SOF_OUT/I2S0_RX_FS_P$28") (pintype "bidirectional"))
      (node (ref "U$65") (pin "P$1") (pinfunction "P$1_P$1") (pintype "bidirectional"))
    )
    (net (code "47") (name "Net-(U$1-PTD1{slash}ADC0_SE5B{slash}SPI0_SCK{slash}~{UART2_CTS})") (class "Default")
      (node (ref "JP1") (pin "1") (pinfunction "1_1") (pintype "passive"))
      (node (ref "U$1") (pin "P$5") (pinfunction "PTD1/ADC0_SE5B/SPI0_SCK/~{UART2_CTS}_P$5") (pintype "bidirectional"))
      (node (ref "U$38") (pin "P$3") (pinfunction "P$2_P$3") (pintype "bidirectional"))
    )
    (net (code "48") (name "Net-(U$1-PTD2{slash}LLWU_P13{slash}SPI0_SOUT{slash}UART2_RX{slash}I2C0_SDA{slash}GPIO4_BSM_DATA)") (class "Default")
      (node (ref "JP1") (pin "2") (pinfunction "2_2") (pintype "passive"))
      (node (ref "U$1") (pin "P$7") (pinfunction "PTD2/LLWU_P13/SPI0_SOUT/UART2_RX/I2C0_SDA/GPIO4_BSM_DATA_P$7") (pintype "bidirectional"))
      (node (ref "U$39") (pin "P$3") (pinfunction "P$2_P$3") (pintype "bidirectional"))
    )
    (net (code "49") (name "Net-(U$1-PTD3{slash}SPI0_SIN{slash}UART2_TX{slash}I2C0_SCL{slash}GPIO5_BSM_CLK)") (class "Default")
      (node (ref "JP1") (pin "3") (pinfunction "3_3") (pintype "passive"))
      (node (ref "U$1") (pin "P$9") (pinfunction "PTD3/SPI0_SIN/UART2_TX/I2C0_SCL/GPIO5_BSM_CLK_P$9") (pintype "bidirectional"))
      (node (ref "U$40") (pin "P$3") (pinfunction "P$2_P$3") (pintype "bidirectional"))
    )
    (net (code "50") (name "Net-(U$1-PTD4{slash}LLWU_P14{slash}MADC0_SE21{slash}SPI0_PCS1{slash}~{UART0_RTS}{slash}FTM0_CH4{slash}EWM_IN{slash}GPIO_BSM_FRAME)") (class "Default")
      (node (ref "JP1") (pin "4") (pinfunction "4_4") (pintype "passive"))
      (node (ref "U$1") (pin "P$11") (pinfunction "PTD4/LLWU_P14/MADC0_SE21/SPI0_PCS1/~{UART0_RTS}/FTM0_CH4/EWM_IN/GPIO_BSM_FRAME_P$11") (pintype "bidirectional"))
      (node (ref "U$41") (pin "P$3") (pinfunction "P$2_P$3") (pintype "bidirectional"))
    )
    (net (code "51") (name "Net-(U$1-PTD5{slash}ADC0_SE6B{slash}SPI0_PCS2{slash}~{UART0_CTS}{slash}~{UART0_COL}{slash}FTM0_CH5{slash}~{EWM_OUT})") (class "Default")
      (node (ref "JP1") (pin "5") (pinfunction "5_5") (pintype "passive"))
      (node (ref "U$1") (pin "P$13") (pinfunction "PTD5/ADC0_SE6B/SPI0_PCS2/~{UART0_CTS}/~{UART0_COL}/FTM0_CH5/~{EWM_OUT}_P$13") (pintype "bidirectional"))
      (node (ref "U$42") (pin "P$3") (pinfunction "P$2_P$3") (pintype "bidirectional"))
    )
    (net (code "52") (name "Net-(U$1-PTD6{slash}LLWU_P15{slash}ADC0_SE7B{slash}SPI0_PCS3{slash}UART0_RX{slash}FTM0_CH6{slash}FTM0_FLT0)") (class "Default")
      (node (ref "JP1") (pin "6") (pinfunction "6_6") (pintype "passive"))
      (node (ref "U$1") (pin "P$15") (pinfunction "PTD6/LLWU_P15/ADC0_SE7B/SPI0_PCS3/UART0_RX/FTM0_CH6/FTM0_FLT0_P$15") (pintype "bidirectional"))
      (node (ref "U$53") (pin "P$3") (pinfunction "P$2_P$3") (pintype "bidirectional"))
    )
    (net (code "53") (name "Net-(U$1-PTD7{slash}MADC0_SE22{slash}CMT_IRO{slash}UART0_TX{slash}FTM0_CH7{slash}FTM0_FLT1)") (class "Default")
      (node (ref "JP1") (pin "7") (pinfunction "7_7") (pintype "passive"))
      (node (ref "U$1") (pin "P$17") (pinfunction "PTD7/MADC0_SE22/CMT_IRO/UART0_TX/FTM0_CH7/FTM0_FLT1_P$17") (pintype "bidirectional"))
      (node (ref "U$43") (pin "P$3") (pinfunction "P$2_P$3") (pintype "bidirectional"))
    )
    (net (code "54") (name "Net-(U$1-PTE0{slash}MADC0_SE10{slash}SPI1_PCS1{slash}UART1_TX{slash}MTRACE_CLKOUT{slash}I2C1_SDA{slash}RTC_CLKOUT)") (class "Default")
      (node (ref "JP1") (pin "8") (pinfunction "8_8") (pintype "passive"))
      (node (ref "U$1") (pin "P$19") (pinfunction "PTE0/MADC0_SE10/SPI1_PCS1/UART1_TX/MTRACE_CLKOUT/I2C1_SDA/RTC_CLKOUT_P$19") (pintype "bidirectional"))
      (node (ref "U$52") (pin "P$3") (pinfunction "P$2_P$3") (pintype "bidirectional"))
    )
    (net (code "55") (name "Net-(U$1-PTE1{slash}LLWU_P0{slash}MADC0_SE11{slash}SPI1_SOUT{slash}UART1_RX{slash}MTRACE_D3{slash}I2C1_SCL{slash}SPI1_SIN)") (class "Default")
      (node (ref "JP1") (pin "9") (pinfunction "9_9") (pintype "passive"))
      (node (ref "U$1") (pin "P$21") (pinfunction "PTE1/LLWU_P0/MADC0_SE11/SPI1_SOUT/UART1_RX/MTRACE_D3/I2C1_SCL/SPI1_SIN_P$21") (pintype "bidirectional"))
      (node (ref "U$44") (pin "P$3") (pinfunction "P$2_P$3") (pintype "bidirectional"))
    )
    (net (code "56") (name "Net-(U$1-PTE2{slash}LLWU_P1{slash}MADC0_DP1{slash}SPI1_SCK{slash}~{UART1_CTS}{slash}MTRACE_D2)") (class "Default")
      (node (ref "JP1") (pin "10") (pinfunction "10_10") (pintype "passive"))
      (node (ref "U$1") (pin "P$23") (pinfunction "PTE2/LLWU_P1/MADC0_DP1/SPI1_SCK/~{UART1_CTS}/MTRACE_D2_P$23") (pintype "bidirectional"))
      (node (ref "U$51") (pin "P$3") (pinfunction "P$2_P$3") (pintype "bidirectional"))
    )
    (net (code "57") (name "Net-(U$1-PTE3{slash}MADC0_DM1{slash}SPI1_SIN{slash}~{UART1_RTS}{slash}MTRACE_D1{slash}SPI1_SOUT)") (class "Default")
      (node (ref "JP1") (pin "11") (pinfunction "11_11") (pintype "passive"))
      (node (ref "U$1") (pin "P$25") (pinfunction "PTE3/MADC0_DM1/SPI1_SIN/~{UART1_RTS}/MTRACE_D1/SPI1_SOUT_P$25") (pintype "bidirectional"))
      (node (ref "U$50") (pin "P$3") (pinfunction "P$2_P$3") (pintype "bidirectional"))
    )
    (net (code "58") (name "Net-(U$1-PTE4{slash}LLWU_P2{slash}SPI1_PCS0{slash}MTRACE_D0)") (class "Default")
      (node (ref "JP1") (pin "12") (pinfunction "12_12") (pintype "passive"))
      (node (ref "U$1") (pin "P$27") (pinfunction "PTE4/LLWU_P2/SPI1_PCS0/MTRACE_D0_P$27") (pintype "bidirectional"))
      (node (ref "U$49") (pin "P$3") (pinfunction "P$2_P$3") (pintype "bidirectional"))
    )
    (net (code "59") (name "Net-(U$1-PTE16{slash}ADC0_SE4A{slash}SPI0_PCS0{slash}UART2_TX{slash}FTM_CLKIN0{slash}FTM0_FLT3)") (class "Default")
      (node (ref "JP1") (pin "13") (pinfunction "13_13") (pintype "passive"))
      (node (ref "U$1") (pin "P$29") (pinfunction "PTE16/ADC0_SE4A/SPI0_PCS0/UART2_TX/FTM_CLKIN0/FTM0_FLT3_P$29") (pintype "bidirectional"))
      (node (ref "U$48") (pin "P$3") (pinfunction "P$2_P$3") (pintype "bidirectional"))
    )
    (net (code "60") (name "Net-(U$1-PTE17{slash}ADC0_SE5A{slash}SPI0_SCK{slash}UART2_RX{slash}FTM_CLKIN1{slash}LPTMR0_ALT3)") (class "Default")
      (node (ref "JP1") (pin "14") (pinfunction "14_14") (pintype "passive"))
      (node (ref "U$1") (pin "P$31") (pinfunction "PTE17/ADC0_SE5A/SPI0_SCK/UART2_RX/FTM_CLKIN1/LPTMR0_ALT3_P$31") (pintype "bidirectional"))
      (node (ref "U$47") (pin "P$3") (pinfunction "P$2_P$3") (pintype "bidirectional"))
    )
    (net (code "61") (name "Net-(U$1-PTE18{slash}ADC0_SE6A{slash}SPI0_SOUT{slash}~{UART2_CTS}{slash}I2C0_SDA)") (class "Default")
      (node (ref "JP1") (pin "15") (pinfunction "15_15") (pintype "passive"))
      (node (ref "U$1") (pin "P$33") (pinfunction "PTE18/ADC0_SE6A/SPI0_SOUT/~{UART2_CTS}/I2C0_SDA_P$33") (pintype "bidirectional"))
      (node (ref "U$46") (pin "P$3") (pinfunction "P$2_P$3") (pintype "bidirectional"))
    )
    (net (code "62") (name "Net-(U$1-PTE19{slash}ADC0_SE7A{slash}SPI0_SIN{slash}~{UART2_RTS}{slash}I2C0_SCL)") (class "Default")
      (node (ref "JP1") (pin "16") (pinfunction "16_16") (pintype "passive"))
      (node (ref "U$1") (pin "P$35") (pinfunction "PTE19/ADC0_SE7A/SPI0_SIN/~{UART2_RTS}/I2C0_SCL_P$35") (pintype "bidirectional"))
      (node (ref "U$45") (pin "P$3") (pinfunction "P$2_P$3") (pintype "bidirectional"))
    )
    (net (code "63") (name "Net-(U$1-~{RESET})") (class "Default")
      (node (ref "JP2") (pin "14") (pinfunction "14_14") (pintype "passive"))
      (node (ref "U$1") (pin "P$6") (pinfunction "~{RESET}_P$6") (pintype "bidirectional"))
      (node (ref "U$19") (pin "P$10") (pinfunction "P$10_P$10") (pintype "bidirectional"))
      (node (ref "U$54") (pin "P$3") (pinfunction "P$2_P$3") (pintype "bidirectional"))
      (node (ref "U$9") (pin "P$2") (pinfunction "2_P$2") (pintype "input"))
    )
    (net (code "64") (name "Net-(U$3-PWR)") (class "Default")
      (node (ref "D2") (pin "A") (pinfunction "A_A") (pintype "passive"))
      (node (ref "U$3") (pin "P$1") (pinfunction "PWR_P$1") (pintype "bidirectional"))
    )
    (net (code "65") (name "Net-(U$13-Pad2)") (class "Default")
      (node (ref "U$13") (pin "2") (pinfunction "2_2") (pintype "passive"))
      (node (ref "U$44") (pin "P$1") (pinfunction "P$1_P$1") (pintype "bidirectional"))
    )
    (net (code "66") (name "Net-(U$16-Pad2)") (class "Default")
      (node (ref "U$16") (pin "2") (pinfunction "2_2") (pintype "passive"))
      (node (ref "U$54") (pin "P$1") (pinfunction "P$1_P$1") (pintype "bidirectional"))
    )
    (net (code "67") (name "Net-(U$17-Pad2)") (class "Default")
      (node (ref "U$17") (pin "2") (pinfunction "2_2") (pintype "passive"))
      (node (ref "U$55") (pin "P$1") (pinfunction "P$1_P$1") (pintype "bidirectional"))
    )
    (net (code "68") (name "Net-(U$18-Pad2)") (class "Default")
      (node (ref "U$18") (pin "2") (pinfunction "2_2") (pintype "passive"))
      (node (ref "U$56") (pin "P$1") (pinfunction "P$1_P$1") (pintype "bidirectional"))
    )
    (net (code "69") (name "Net-(U$20-Pad2)") (class "Default")
      (node (ref "U$20") (pin "2") (pinfunction "2_2") (pintype "passive"))
      (node (ref "U$57") (pin "P$1") (pinfunction "P$1_P$1") (pintype "bidirectional"))
    )
    (net (code "70") (name "Net-(U$21-Pad2)") (class "Default")
      (node (ref "U$21") (pin "2") (pinfunction "2_2") (pintype "passive"))
      (node (ref "U$58") (pin "P$1") (pinfunction "P$1_P$1") (pintype "bidirectional"))
    )
    (net (code "71") (name "Net-(U$22-Pad2)") (class "Default")
      (node (ref "U$22") (pin "2") (pinfunction "2_2") (pintype "passive"))
      (node (ref "U$45") (pin "P$1") (pinfunction "P$1_P$1") (pintype "bidirectional"))
    )
    (net (code "72") (name "Net-(U$23-Pad2)") (class "Default")
      (node (ref "U$23") (pin "2") (pinfunction "2_2") (pintype "passive"))
      (node (ref "U$51") (pin "P$1") (pinfunction "P$1_P$1") (pintype "bidirectional"))
    )
    (net (code "73") (name "Net-(U$25-Pad2)") (class "Default")
      (node (ref "U$25") (pin "2") (pinfunction "2_2") (pintype "passive"))
      (node (ref "U$38") (pin "P$1") (pinfunction "P$1_P$1") (pintype "bidirectional"))
    )
    (net (code "74") (name "Net-(U$26-Pad2)") (class "Default")
      (node (ref "U$26") (pin "2") (pinfunction "2_2") (pintype "passive"))
      (node (ref "U$39") (pin "P$1") (pinfunction "P$1_P$1") (pintype "bidirectional"))
    )
    (net (code "75") (name "Net-(U$27-Pad2)") (class "Default")
      (node (ref "U$27") (pin "2") (pinfunction "2_2") (pintype "passive"))
      (node (ref "U$40") (pin "P$1") (pinfunction "P$1_P$1") (pintype "bidirectional"))
    )
    (net (code "76") (name "Net-(U$28-Pad2)") (class "Default")
      (node (ref "U$28") (pin "2") (pinfunction "2_2") (pintype "passive"))
      (node (ref "U$41") (pin "P$1") (pinfunction "P$1_P$1") (pintype "bidirectional"))
    )
    (net (code "77") (name "Net-(U$29-Pad2)") (class "Default")
      (node (ref "U$29") (pin "2") (pinfunction "2_2") (pintype "passive"))
      (node (ref "U$42") (pin "P$1") (pinfunction "P$1_P$1") (pintype "bidirectional"))
    )
    (net (code "78") (name "Net-(U$30-Pad2)") (class "Default")
      (node (ref "U$30") (pin "2") (pinfunction "2_2") (pintype "passive"))
      (node (ref "U$53") (pin "P$1") (pinfunction "P$1_P$1") (pintype "bidirectional"))
    )
    (net (code "79") (name "Net-(U$31-Pad2)") (class "Default")
      (node (ref "U$31") (pin "2") (pinfunction "2_2") (pintype "passive"))
      (node (ref "U$43") (pin "P$1") (pinfunction "P$1_P$1") (pintype "bidirectional"))
    )
    (net (code "80") (name "Net-(U$32-Pad2)") (class "Default")
      (node (ref "U$32") (pin "2") (pinfunction "2_2") (pintype "passive"))
      (node (ref "U$52") (pin "P$1") (pinfunction "P$1_P$1") (pintype "bidirectional"))
    )
    (net (code "81") (name "Net-(U$33-Pad2)") (class "Default")
      (node (ref "U$33") (pin "2") (pinfunction "2_2") (pintype "passive"))
      (node (ref "U$50") (pin "P$1") (pinfunction "P$1_P$1") (pintype "bidirectional"))
    )
    (net (code "82") (name "Net-(U$34-Pad2)") (class "Default")
      (node (ref "U$34") (pin "2") (pinfunction "2_2") (pintype "passive"))
      (node (ref "U$49") (pin "P$1") (pinfunction "P$1_P$1") (pintype "bidirectional"))
    )
    (net (code "83") (name "Net-(U$35-Pad2)") (class "Default")
      (node (ref "U$35") (pin "2") (pinfunction "2_2") (pintype "passive"))
      (node (ref "U$48") (pin "P$1") (pinfunction "P$1_P$1") (pintype "bidirectional"))
    )
    (net (code "84") (name "Net-(U$36-Pad2)") (class "Default")
      (node (ref "U$36") (pin "2") (pinfunction "2_2") (pintype "passive"))
      (node (ref "U$47") (pin "P$1") (pinfunction "P$1_P$1") (pintype "bidirectional"))
    )
    (net (code "85") (name "Net-(U$37-Pad2)") (class "Default")
      (node (ref "U$37") (pin "2") (pinfunction "2_2") (pintype "passive"))
      (node (ref "U$46") (pin "P$1") (pinfunction "P$1_P$1") (pintype "bidirectional"))
    )
    (net (code "86") (name "Net-(U$59-P$2)") (class "Default")
      (node (ref "U$4") (pin "2") (pinfunction "2_2") (pintype "passive"))
      (node (ref "U$59") (pin "P$3") (pinfunction "P$2_P$3") (pintype "bidirectional"))
    )
    (net (code "87") (name "Net-(U$60-P$2)") (class "Default")
      (node (ref "U$5") (pin "2") (pinfunction "2_2") (pintype "passive"))
      (node (ref "U$60") (pin "P$3") (pinfunction "P$2_P$3") (pintype "bidirectional"))
    )
    (net (code "88") (name "Net-(U$61-P$2)") (class "Default")
      (node (ref "U$6") (pin "2") (pinfunction "2_2") (pintype "passive"))
      (node (ref "U$61") (pin "P$3") (pinfunction "P$2_P$3") (pintype "bidirectional"))
    )
    (net (code "89") (name "Net-(U$62-P$2)") (class "Default")
      (node (ref "U$62") (pin "P$3") (pinfunction "P$2_P$3") (pintype "bidirectional"))
      (node (ref "U$7") (pin "2") (pinfunction "2_2") (pintype "passive"))
    )
    (net (code "90") (name "Net-(U$63-P$2)") (class "Default")
      (node (ref "U$63") (pin "P$3") (pinfunction "P$2_P$3") (pintype "bidirectional"))
      (node (ref "U$8") (pin "2") (pinfunction "2_2") (pintype "passive"))
    )
    (net (code "91") (name "Net-(U$64-P$2)") (class "Default")
      (node (ref "U$14") (pin "2") (pinfunction "2_2") (pintype "passive"))
      (node (ref "U$64") (pin "P$3") (pinfunction "P$2_P$3") (pintype "bidirectional"))
    )
    (net (code "92") (name "Net-(U$65-P$2)") (class "Default")
      (node (ref "U$15") (pin "2") (pinfunction "2_2") (pintype "passive"))
      (node (ref "U$65") (pin "P$3") (pinfunction "P$2_P$3") (pintype "bidirectional"))
    )
    (net (code "93") (name "Net-(U$68-P$2)") (class "Default")
      (node (ref "U$66") (pin "2") (pinfunction "2_2") (pintype "passive"))
      (node (ref "U$68") (pin "P$3") (pinfunction "P$2_P$3") (pintype "bidirectional"))
    )
    (net (code "94") (name "Net-(U$69-P$2)") (class "Default")
      (node (ref "U$67") (pin "2") (pinfunction "2_2") (pintype "passive"))
      (node (ref "U$69") (pin "P$3") (pinfunction "P$2_P$3") (pintype "bidirectional"))
    )
    (net (code "95") (name "Net-(X1-VBUS)") (class "Default")
      (node (ref "D1") (pin "A") (pinfunction "A_A") (pintype "passive"))
      (node (ref "X1") (pin "VCC") (pinfunction "VBUS_VCC") (pintype "bidirectional"))
    )
    (net (code "96") (name "V+") (class "Default")
      (node (ref "C1") (pin "1") (pinfunction "1_1") (pintype "passive"))
      (node (ref "D1") (pin "C") (pinfunction "C_C") (pintype "passive"))
      (node (ref "D2") (pin "C") (pinfunction "C_C") (pintype "passive"))
      (node (ref "IC1") (pin "3") (pinfunction "IN_3") (pintype "input"))
      (node (ref "JP5") (pin "1") (pinfunction "1_1") (pintype "passive"))
      (node (ref "JP5") (pin "2") (pinfunction "2_2") (pintype "passive"))
      (node (ref "JP5") (pin "3") (pinfunction "3_3") (pintype "passive"))
      (node (ref "U$10") (pin "2") (pinfunction "2_2") (pintype "passive"))
      (node (ref "U$11") (pin "2") (pinfunction "2_2") (pintype "passive"))
      (node (ref "U$12") (pin "2") (pinfunction "2_2") (pintype "passive"))
    )
    (net (code "97") (name "unconnected-(U$1-NC-PadP$34)") (class "Default")
      (node (ref "U$1") (pin "P$34") (pinfunction "NC_P$34") (pintype "bidirectional"))
    )
    (net (code "98") (name "unconnected-(U$1-NC-PadP$36)") (class "Default")
      (node (ref "U$1") (pin "P$36") (pinfunction "NC_P$36") (pintype "bidirectional"))
    )
    (net (code "99") (name "unconnected-(U$1-PadP$41)") (class "Default")
      (node (ref "U$1") (pin "P$41") (pinfunction "P$41_P$41") (pintype "bidirectional"))
    )
    (net (code "100") (name "unconnected-(U$1-PadP$42)") (class "Default")
      (node (ref "U$1") (pin "P$42") (pinfunction "P$42_P$42") (pintype "bidirectional"))
    )
    (net (code "101") (name "unconnected-(U$1-VIN-PadP$38)") (class "Default")
      (node (ref "U$1") (pin "P$38") (pinfunction "VIN_P$38") (pintype "bidirectional"))
    )
    (net (code "102") (name "unconnected-(U$1-VIN-PadP$40)") (class "Default")
      (node (ref "U$1") (pin "P$40") (pinfunction "VIN_P$40") (pintype "bidirectional"))
    )
    (net (code "103") (name "unconnected-(U$3-GNDBREAK-PadP$3)") (class "Default")
      (node (ref "U$3") (pin "P$3") (pinfunction "GNDBREAK_P$3") (pintype "bidirectional"))
    )
    (net (code "104") (name "unconnected-(U$19-PadP$7)") (class "Default")
      (node (ref "U$19") (pin "P$7") (pinfunction "P$7_P$7") (pintype "bidirectional"))
    )
    (net (code "105") (name "unconnected-(U$19-PadP$11)") (class "Default")
      (node (ref "U$19") (pin "P$11") (pinfunction "P$11_P$11") (pintype "bidirectional"))
    )
    (net (code "106") (name "unconnected-(U$19-PadP$12)") (class "Default")
      (node (ref "U$19") (pin "P$12") (pinfunction "P$12_P$12") (pintype "bidirectional"))
    )
    (net (code "107") (name "unconnected-(U$19-PadP$13)") (class "Default")
      (node (ref "U$19") (pin "P$13") (pinfunction "P$13_P$13") (pintype "bidirectional"))
    )
    (net (code "108") (name "unconnected-(U$19-PadP$14)") (class "Default")
      (node (ref "U$19") (pin "P$14") (pinfunction "P$14_P$14") (pintype "bidirectional"))
    )
    (net (code "109") (name "unconnected-(U$19-PadP$16)") (class "Default")
      (node (ref "U$19") (pin "P$16") (pinfunction "P$16_P$16") (pintype "bidirectional"))
    )
    (net (code "110") (name "unconnected-(U$19-PadP$18)") (class "Default")
      (node (ref "U$19") (pin "P$18") (pinfunction "P$18_P$18") (pintype "bidirectional"))
    )
    (net (code "111") (name "unconnected-(U$19-PadP$20)") (class "Default")
      (node (ref "U$19") (pin "P$20") (pinfunction "P$20_P$20") (pintype "bidirectional"))
    )
    (net (code "112") (name "unconnected-(X1-PadD+)") (class "Default")
      (node (ref "X1") (pin "D+") (pinfunction "D+_D+") (pintype "bidirectional"))
    )
    (net (code "113") (name "unconnected-(X1-PadD-)") (class "Default")
      (node (ref "X1") (pin "D-") (pinfunction "D-_D-") (pintype "bidirectional"))
    )
  )
)
